# 6coils-1-discrete.net
KiCad netlist of a schematic drawn in EasyEDA
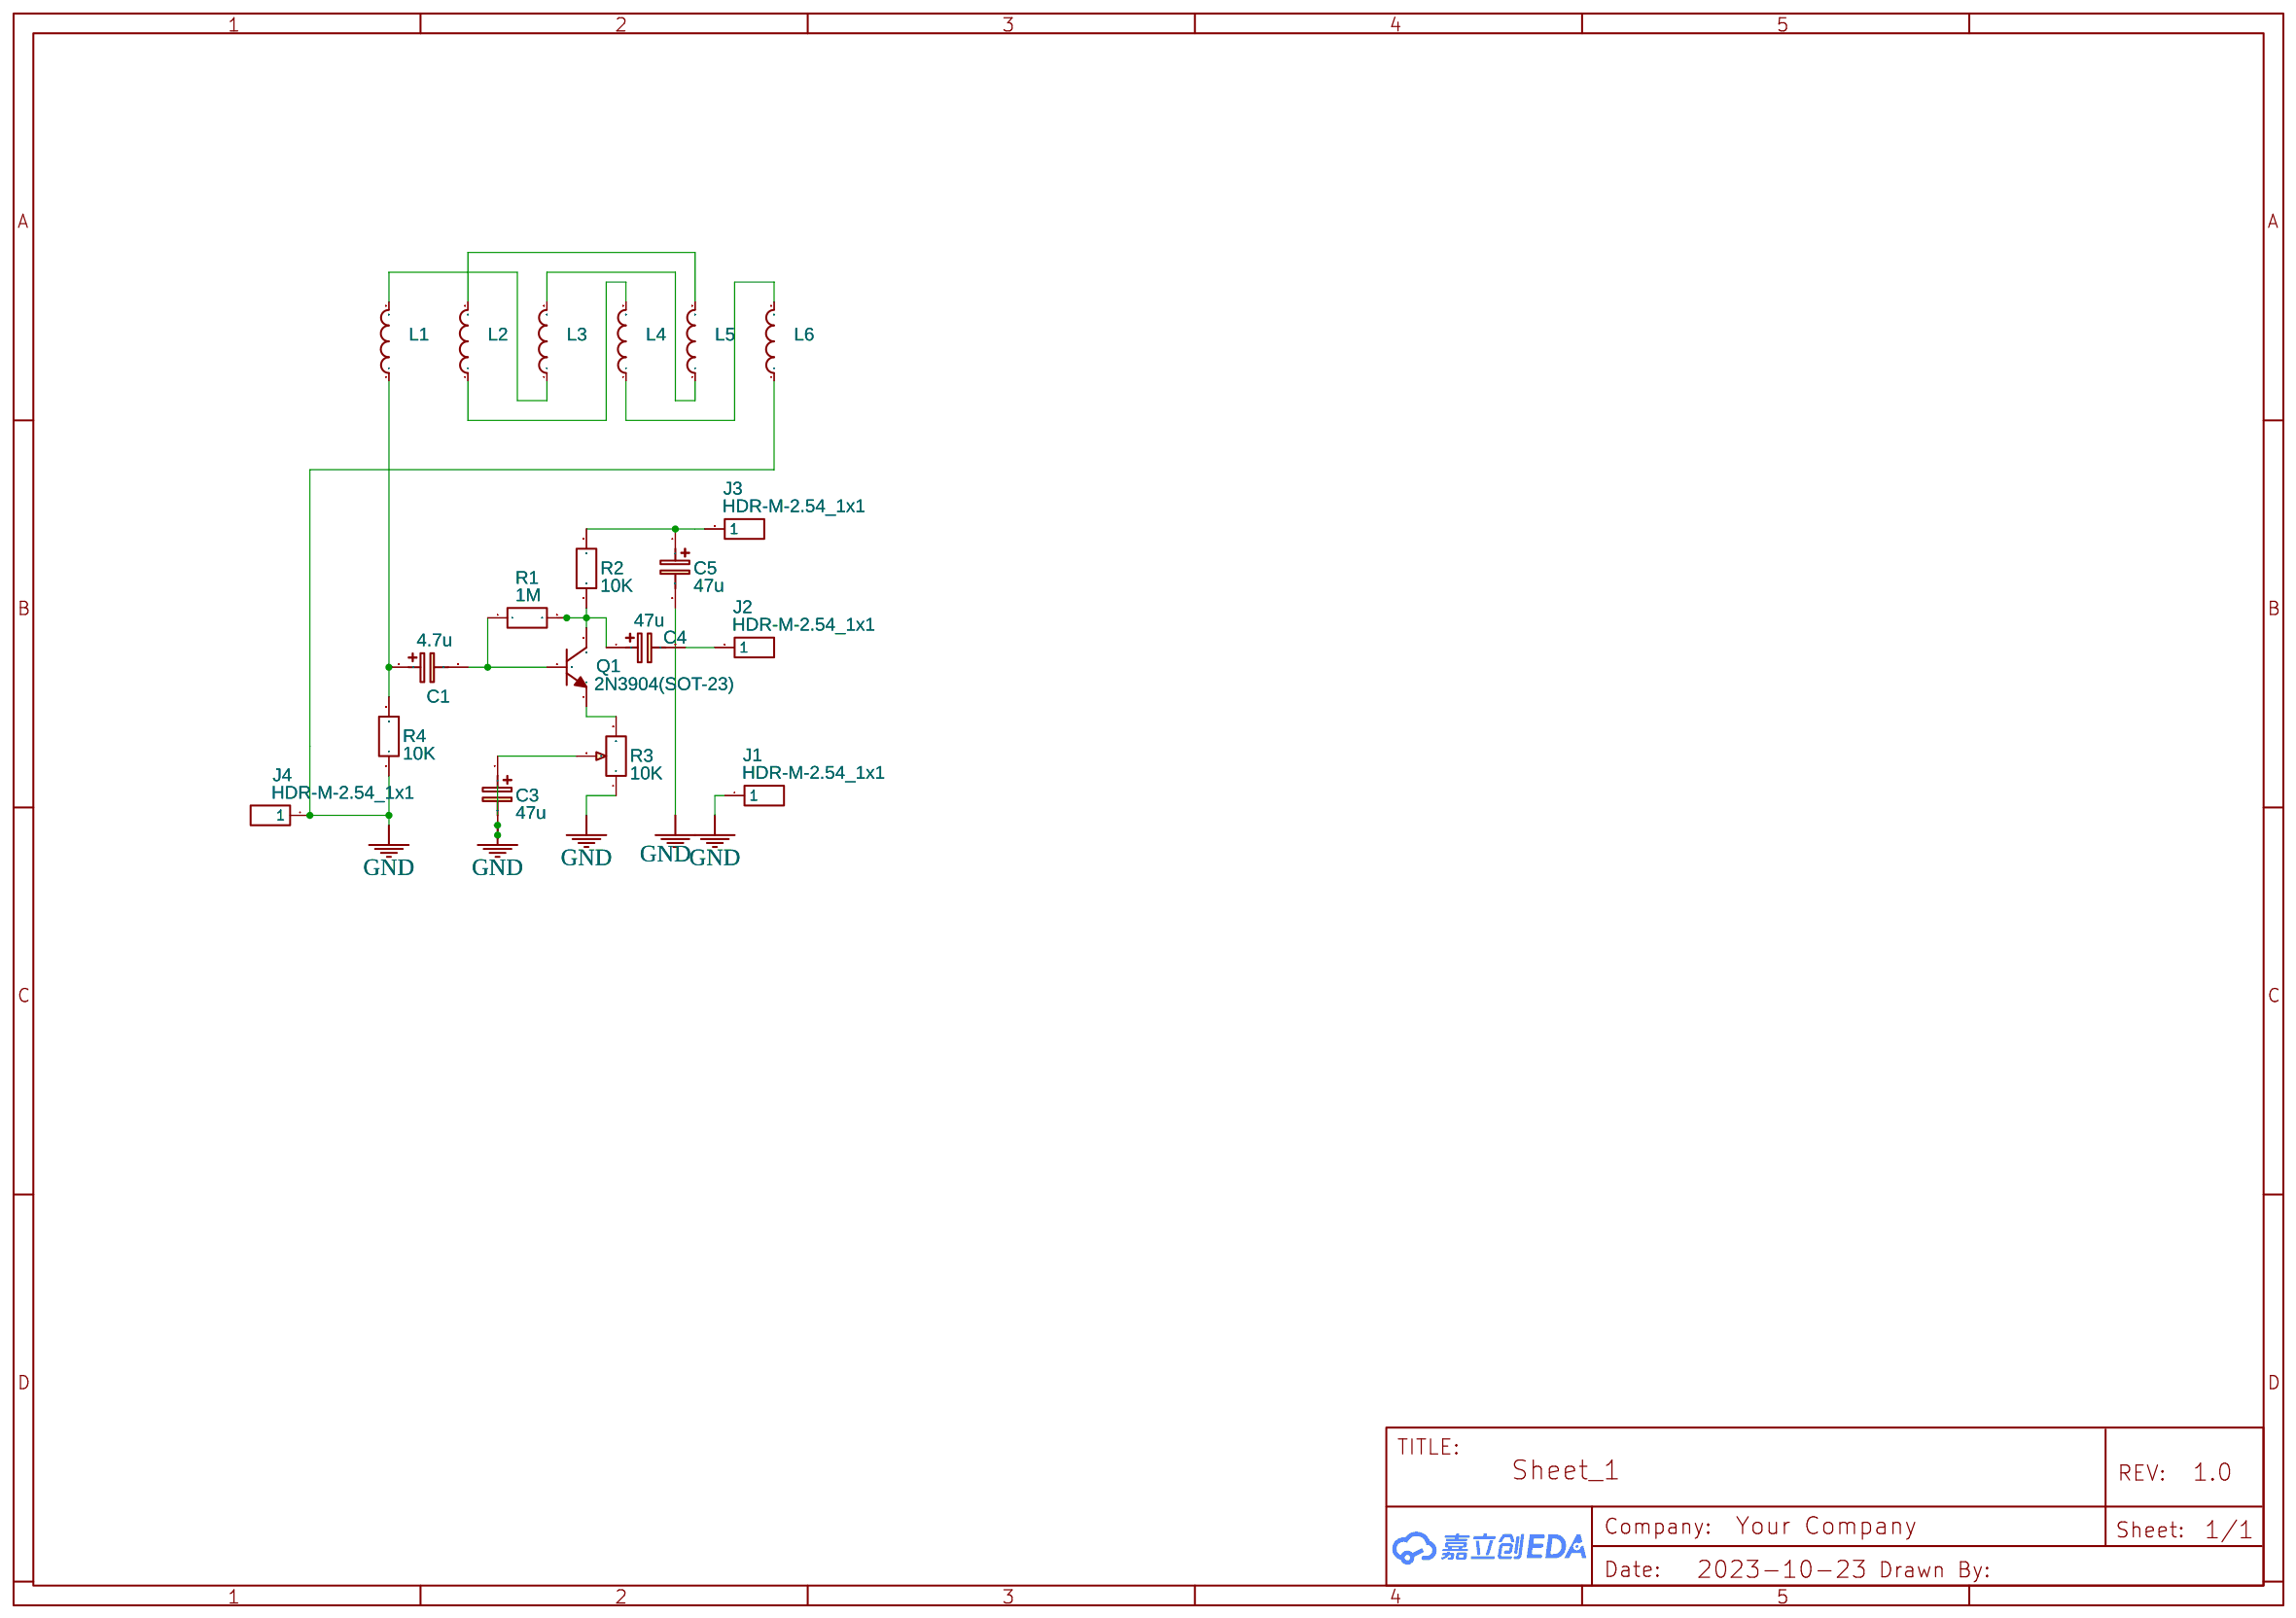
[diagram p0: schematic sheet]

(export (version "E")
  (design (tool "Eeschema 10.0.6"))
  (components
    (comp (ref "C1") (value "4.7u") (libsource (lib "") (part "C_Tan_SMD_A_EU_1")))
    (comp (ref "C3") (value "47u") (libsource (lib "") (part "C_Tan_SMD_A_EU")))
    (comp (ref "C4") (value "47u") (libsource (lib "") (part "C_Tan_SMD_A_EU_3")))
    (comp (ref "C5") (value "47u") (libsource (lib "") (part "C_Tan_SMD_A_EU_2")))
    (comp (ref "J1")
      (value "HDR-M-2.54_1x1")
      (fields (field (name "BOM_Supplier Part") "C81276"))
      (libsource (lib "") (part "HDR-M-2.54_1x1"))
    )
    (comp (ref "J2")
      (value "HDR-M-2.54_1x1")
      (fields (field (name "BOM_Supplier Part") "C81276"))
      (libsource (lib "") (part "HDR-M-2.54_1x1"))
    )
    (comp (ref "J3")
      (value "HDR-M-2.54_1x1")
      (fields (field (name "BOM_Supplier Part") "C81276"))
      (libsource (lib "") (part "HDR-M-2.54_1x1"))
    )
    (comp (ref "J4")
      (value "HDR-M-2.54_1x1")
      (fields (field (name "BOM_Supplier Part") "C81276"))
      (libsource (lib "") (part "HDR-M-2.54_1x1_1"))
    )
    (comp (ref "L1")
      (value "INDUCTOR_SMD:L_COILCRAFT_XXL4040")
      (fields (field (name "Manufacturer Part") "Inductor_SMD:L_Coilcraft_XxL4040"))
      (libsource (lib "") (part "INDUCTOR_SMD{colon}L_COILCRAFT_XXL4040_1"))
    )
    (comp (ref "L2")
      (value "INDUCTOR_SMD:L_COILCRAFT_XXL4040")
      (fields (field (name "Manufacturer Part") "Inductor_SMD:L_Coilcraft_XxL4040"))
      (libsource (lib "") (part "INDUCTOR_SMD{colon}L_COILCRAFT_XXL4040_1"))
    )
    (comp (ref "L3")
      (value "INDUCTOR_SMD:L_COILCRAFT_XXL4040")
      (fields (field (name "Manufacturer Part") "Inductor_SMD:L_Coilcraft_XxL4040"))
      (libsource (lib "") (part "INDUCTOR_SMD{colon}L_COILCRAFT_XXL4040"))
    )
    (comp (ref "L4")
      (value "INDUCTOR_SMD:L_COILCRAFT_XXL4040")
      (fields (field (name "Manufacturer Part") "Inductor_SMD:L_Coilcraft_XxL4040"))
      (libsource (lib "") (part "INDUCTOR_SMD{colon}L_COILCRAFT_XXL4040"))
    )
    (comp (ref "L5")
      (value "INDUCTOR_SMD:L_COILCRAFT_XXL4040")
      (fields (field (name "Manufacturer Part") "Inductor_SMD:L_Coilcraft_XxL4040"))
      (libsource (lib "") (part "INDUCTOR_SMD{colon}L_COILCRAFT_XXL4040"))
    )
    (comp (ref "L6")
      (value "INDUCTOR_SMD:L_COILCRAFT_XXL4040")
      (fields (field (name "Manufacturer Part") "Inductor_SMD:L_Coilcraft_XxL4040"))
      (libsource (lib "") (part "INDUCTOR_SMD{colon}L_COILCRAFT_XXL4040"))
    )
    (comp (ref "Q1")
      (value "2N3904(SOT-23)")
      (fields
        (field (name "BOM_Manufacturer Part") "2n3904S-RTK/PS")
        (field (name "BOM_Supplier Part") "C18536")
      )
      (libsource (lib "") (part "2N3904(SOT-23)"))
    )
    (comp (ref "R1") (value "1M") (libsource (lib "") (part "R_0603_EU_1")))
    (comp (ref "R2") (value "10K") (libsource (lib "") (part "R_0603_EU")))
    (comp (ref "R3")
      (value "10K")
      (fields (field (name "Manufacturer Part") "RM063-103 10K") (field (name "Manufacturer") "JML"))
      (libsource (lib "") (part "RM063-103 10K"))
    )
    (comp (ref "R4") (value "10K") (libsource (lib "") (part "R_0603_EU")))
  )
  (nets
    (net (code "1") (name "GND") (class "Default")
      (node (ref "C3") (pin "2") (pinfunction "2_2") (pintype "unspecified"))
      (node (ref "C5") (pin "2") (pinfunction "2_2") (pintype "unspecified"))
      (node (ref "J1") (pin "1") (pinfunction "1_1") (pintype "input"))
      (node (ref "J4") (pin "1") (pinfunction "1_1") (pintype "input"))
      (node (ref "L6") (pin "1") (pinfunction "1_1") (pintype "unspecified"))
      (node (ref "R3") (pin "1") (pinfunction "1_1") (pintype "input"))
      (node (ref "R4") (pin "1") (pinfunction "1_1") (pintype "unspecified"))
    )
    (net (code "2") (name "Net-(C1-Pad1)") (class "Default")
      (node (ref "C1") (pin "1") (pinfunction "1_1") (pintype "unspecified"))
      (node (ref "L1") (pin "1") (pinfunction "1_1") (pintype "unspecified"))
      (node (ref "R4") (pin "2") (pinfunction "2_2") (pintype "unspecified"))
    )
    (net (code "3") (name "Net-(C3-Pad1)") (class "Default")
      (node (ref "C3") (pin "1") (pinfunction "1_1") (pintype "unspecified"))
      (node (ref "R3") (pin "2") (pinfunction "2_2") (pintype "input"))
    )
    (net (code "4") (name "Net-(C4-Pad2)") (class "Default")
      (node (ref "C4") (pin "2") (pinfunction "2_2") (pintype "unspecified"))
      (node (ref "J2") (pin "1") (pinfunction "1_1") (pintype "input"))
    )
    (net (code "5") (name "Net-(C5-Pad1)") (class "Default")
      (node (ref "C5") (pin "1") (pinfunction "1_1") (pintype "unspecified"))
      (node (ref "J3") (pin "1") (pinfunction "1_1") (pintype "input"))
      (node (ref "R2") (pin "2") (pinfunction "2_2") (pintype "unspecified"))
    )
    (net (code "6") (name "Net-(L1-Pad2)") (class "Default")
      (node (ref "L1") (pin "2") (pinfunction "2_2") (pintype "unspecified"))
      (node (ref "L3") (pin "1") (pinfunction "1_1") (pintype "unspecified"))
    )
    (net (code "7") (name "Net-(L2-Pad1)") (class "Default")
      (node (ref "L2") (pin "1") (pinfunction "1_1") (pintype "unspecified"))
      (node (ref "L4") (pin "2") (pinfunction "2_2") (pintype "unspecified"))
    )
    (net (code "8") (name "Net-(L2-Pad2)") (class "Default")
      (node (ref "L2") (pin "2") (pinfunction "2_2") (pintype "unspecified"))
      (node (ref "L5") (pin "2") (pinfunction "2_2") (pintype "unspecified"))
    )
    (net (code "9") (name "Net-(L3-Pad2)") (class "Default")
      (node (ref "L3") (pin "2") (pinfunction "2_2") (pintype "unspecified"))
      (node (ref "L5") (pin "1") (pinfunction "1_1") (pintype "unspecified"))
    )
    (net (code "10") (name "Net-(L4-Pad1)") (class "Default")
      (node (ref "L4") (pin "1") (pinfunction "1_1") (pintype "unspecified"))
      (node (ref "L6") (pin "2") (pinfunction "2_2") (pintype "unspecified"))
    )
    (net (code "11") (name "Net-(Q1-B)") (class "Default")
      (node (ref "C1") (pin "2") (pinfunction "2_2") (pintype "unspecified"))
      (node (ref "Q1") (pin "2") (pinfunction "B_2") (pintype "input"))
      (node (ref "R1") (pin "1") (pinfunction "1_1") (pintype "unspecified"))
    )
    (net (code "12") (name "Net-(Q1-C)") (class "Default")
      (node (ref "C4") (pin "1") (pinfunction "1_1") (pintype "unspecified"))
      (node (ref "Q1") (pin "3") (pinfunction "C_3") (pintype "input"))
      (node (ref "R1") (pin "2") (pinfunction "2_2") (pintype "unspecified"))
      (node (ref "R2") (pin "1") (pinfunction "1_1") (pintype "unspecified"))
    )
    (net (code "13") (name "Net-(Q1-E)") (class "Default")
      (node (ref "Q1") (pin "1") (pinfunction "E_1") (pintype "input"))
      (node (ref "R3") (pin "3") (pinfunction "3_3") (pintype "input"))
    )
  )
)
